# LDO.net
KiCad netlist of a schematic drawn in Altium Designer
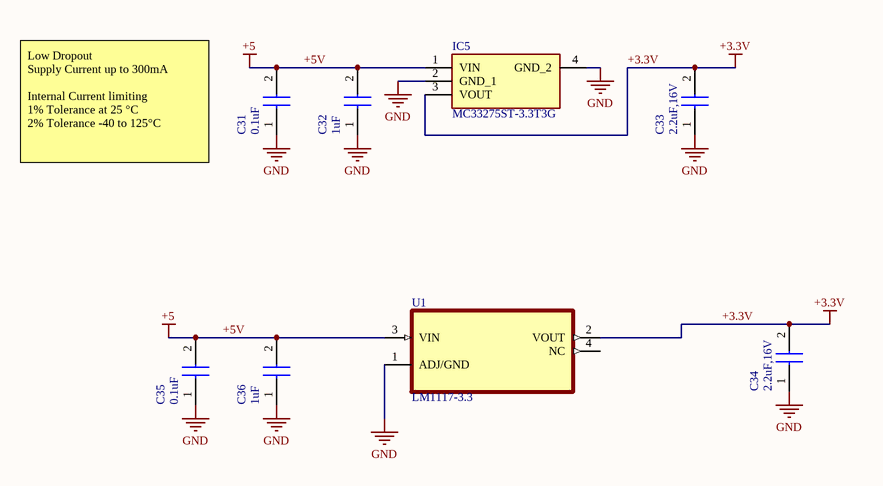
[diagram p0: LDO.SchDoc]

(export (version "E")
  (design (tool "Eeschema 10.0.6"))
  (components
    (comp (ref "C31")
      (value "0.1uF")
      (footprint "SamacSys:CAPC1608X90N")
      (description "Capacitor")
      (fields
        (field (name "MANUFACTURER_PART_NUMBER") "EMK107B7104KAHT")
        (field (name "MOUSER PART NUMBER") "963-EMK107B7104KAHT")
      )
      (libsource (lib "Schlib1") (part "EMK107B7104KAHT"))
    )
    (comp (ref "C32")
      (value "1uF")
      (footprint "SamacSys:CAPC1608X90N")
      (description "Capacitor")
      (fields
        (field (name "MANUFACTURER_PART_NUMBER") "EMK107B7104KAHT")
        (field (name "MOUSER PART NUMBER") "963-EMK107B7104KAHT")
      )
      (libsource (lib "Schlib1") (part "EMK107B7104KAHT"))
    )
    (comp (ref "C33")
      (value "2.2uF,16V")
      (footprint "SamacSys:CAPC1608X90N")
      (description "Capacitor")
      (fields
        (field (name "MANUFACTURER_PART_NUMBER") "EMK107B7104KAHT")
        (field (name "MOUSER PART NUMBER") "963-EMK107B7104KAHT")
      )
      (libsource (lib "Schlib1") (part "EMK107B7104KAHT"))
    )
    (comp (ref "C34")
      (value "2.2uF,16V")
      (footprint "SamacSys:CAPC1608X90N")
      (description "Capacitor")
      (fields
        (field (name "MANUFACTURER_PART_NUMBER") "EMK107B7104KAHT")
        (field (name "MOUSER PART NUMBER") "963-EMK107B7104KAHT")
      )
      (libsource (lib "Schlib1") (part "EMK107B7104KAHT"))
    )
    (comp (ref "C35")
      (value "0.1uF")
      (footprint "SamacSys:CAPC1608X90N")
      (description "Capacitor")
      (fields
        (field (name "MANUFACTURER_PART_NUMBER") "EMK107B7104KAHT")
        (field (name "MOUSER PART NUMBER") "963-EMK107B7104KAHT")
      )
      (libsource (lib "Schlib1") (part "EMK107B7104KAHT"))
    )
    (comp (ref "C36")
      (value "1uF")
      (footprint "SamacSys:CAPC1608X90N")
      (description "Capacitor")
      (fields
        (field (name "MANUFACTURER_PART_NUMBER") "EMK107B7104KAHT")
        (field (name "MOUSER PART NUMBER") "963-EMK107B7104KAHT")
      )
      (libsource (lib "Schlib1") (part "EMK107B7104KAHT"))
    )
    (comp (ref "IC5")
      (value "MC33275ST-3.3T3G")
      (footprint "SOT230P700X175-4N")
      (description "Integrated Circuit")
      (fields (field (name "MOUSER PART NUMBER") "863-MC33275ST-3.3T3G"))
      (libsource (lib "Schlib1") (part "MC33275ST-3.3T3G"))
    )
    (comp (ref "U1")
      (value "LM1117-3.3")
      (footprint "SOT230")
      (description "Regulador de tensÃ£o linear IC 1 Output 800mA SOT-223-4")
      (fields (field (name "MF") "Texas Instruments"))
      (libsource (lib "Schlib1") (part "LM1117-3.3"))
    )
  )
  (nets
    (net (code "1") (name "+3.3V") (class "Default")
      (node (ref "C33") (pin "2") (pinfunction "2_2") (pintype "passive"))
      (node (ref "C34") (pin "2") (pinfunction "2_2") (pintype "passive"))
      (node (ref "IC5") (pin "3") (pinfunction "VOUT_3") (pintype "passive"))
      (node (ref "U1") (pin "2") (pinfunction "VOUT_2") (pintype "output"))
    )
    (net (code "2") (name "+5") (class "Default")
      (node (ref "C31") (pin "2") (pinfunction "2_2") (pintype "passive"))
      (node (ref "C32") (pin "2") (pinfunction "2_2") (pintype "passive"))
      (node (ref "C35") (pin "2") (pinfunction "2_2") (pintype "passive"))
      (node (ref "C36") (pin "2") (pinfunction "2_2") (pintype "passive"))
      (node (ref "IC5") (pin "1") (pinfunction "VIN_1") (pintype "passive"))
      (node (ref "U1") (pin "3") (pinfunction "VIN_3") (pintype "input"))
    )
    (net (code "3") (name "GND") (class "Default")
      (node (ref "C31") (pin "1") (pinfunction "1_1") (pintype "passive"))
      (node (ref "C32") (pin "1") (pinfunction "1_1") (pintype "passive"))
      (node (ref "C33") (pin "1") (pinfunction "1_1") (pintype "passive"))
      (node (ref "C34") (pin "1") (pinfunction "1_1") (pintype "passive"))
      (node (ref "C35") (pin "1") (pinfunction "1_1") (pintype "passive"))
      (node (ref "C36") (pin "1") (pinfunction "1_1") (pintype "passive"))
      (node (ref "IC5") (pin "2") (pinfunction "GND_1_2") (pintype "passive"))
      (node (ref "IC5") (pin "4") (pinfunction "GND_2_4") (pintype "passive"))
      (node (ref "U1") (pin "1") (pinfunction "ADJ/GND_1") (pintype "passive"))
    )
    (net (code "4") (name "unconnected-(U1-NC-Pad4)") (class "Default")
      (node (ref "U1") (pin "4") (pinfunction "NC_4") (pintype "output"))
    )
  )
)
